# POWER.net
KiCad netlist of a schematic drawn in Altium Designer
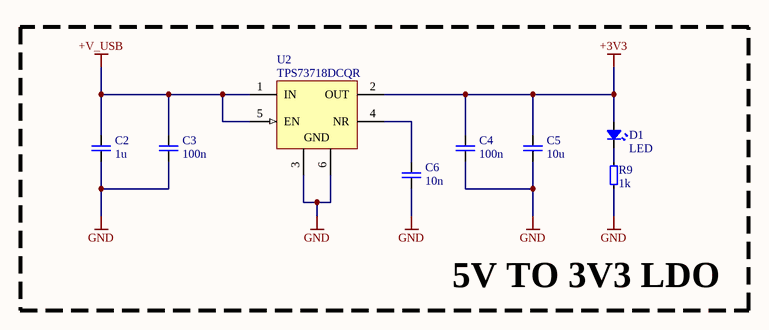
[diagram p0: POWER.SchDoc]

(export (version "E")
  (design (tool "Eeschema 10.0.6"))
  (components
    (comp (ref "C2")
      (value "1u")
      (footprint "C0603")
      (description "Generic 0603 SMD Ceramic Capacitor")
      (libsource (lib "PolSl Racing - Electrical") (part "Capacitor"))
    )
    (comp (ref "C3")
      (value "100n")
      (footprint "C0603")
      (description "Generic 0603 SMD Ceramic Capacitor")
      (libsource (lib "PolSl Racing - Electrical") (part "Capacitor"))
    )
    (comp (ref "C4")
      (value "100n")
      (footprint "C0603")
      (description "Generic 0603 SMD Ceramic Capacitor")
      (libsource (lib "PolSl Racing - Electrical") (part "Capacitor"))
    )
    (comp (ref "C5")
      (value "10u")
      (footprint "C0805")
      (description "Generic 0805 SMD Ceramic Capacitor")
      (libsource (lib "PolSl Racing - Electrical") (part "Capacitor"))
    )
    (comp (ref "C6")
      (value "10n")
      (footprint "C0603")
      (description "Generic 0603 SMD Ceramic Capacitor")
      (libsource (lib "PolSl Racing - Electrical") (part "Capacitor"))
    )
    (comp (ref "D1")
      (value "LED")
      (footprint "LED0603")
      (description "0603 LED")
      (libsource (lib "PolSl Racing - Electrical") (part "LED"))
    )
    (comp (ref "R9")
      (value "1k")
      (footprint "R0603")
      (description "Generic 0603 SMD Resistor")
      (libsource (lib "PolSl Racing - Electrical") (part "Resistor"))
    )
    (comp (ref "U2")
      (value "TPS73718DCQR")
      (footprint "DCQ0006A_L")
      (fields (field (name "MANUFACTURER") "Texas Instruments"))
      (libsource (lib "Altium Content Vault") (part "TI-TPS73XXXDCQ6"))
    )
  )
  (nets
    (net (code "1") (name "+3V3") (class "Default")
      (node (ref "C4") (pin "2") (pinfunction "2_2") (pintype "passive"))
      (node (ref "C5") (pin "2") (pinfunction "2_2") (pintype "passive"))
      (node (ref "D1") (pin "A") (pinfunction "A_A") (pintype "passive"))
      (node (ref "U2") (pin "2") (pinfunction "OUT_2") (pintype "power_in"))
    )
    (net (code "2") (name "+V_USB") (class "Default")
      (node (ref "C2") (pin "2") (pinfunction "2_2") (pintype "passive"))
      (node (ref "C3") (pin "2") (pinfunction "2_2") (pintype "passive"))
      (node (ref "U2") (pin "1") (pinfunction "IN_1") (pintype "power_in"))
      (node (ref "U2") (pin "5") (pinfunction "EN_5") (pintype "input"))
    )
    (net (code "3") (name "GND") (class "Default")
      (node (ref "C2") (pin "1") (pinfunction "1_1") (pintype "passive"))
      (node (ref "C3") (pin "1") (pinfunction "1_1") (pintype "passive"))
      (node (ref "C4") (pin "1") (pinfunction "1_1") (pintype "passive"))
      (node (ref "C5") (pin "1") (pinfunction "1_1") (pintype "passive"))
      (node (ref "C6") (pin "1") (pinfunction "1_1") (pintype "passive"))
      (node (ref "R9") (pin "1") (pinfunction "1_1") (pintype "passive"))
      (node (ref "U2") (pin "3") (pinfunction "GND_3") (pintype "power_in"))
      (node (ref "U2") (pin "6") (pinfunction "GND_6") (pintype "power_in"))
    )
    (net (code "4") (name "Net-(D1-PadK)") (class "Default")
      (node (ref "D1") (pin "K") (pinfunction "K_K") (pintype "passive"))
      (node (ref "R9") (pin "2") (pinfunction "2_2") (pintype "passive"))
    )
    (net (code "5") (name "Net-(U2-NR)") (class "Default")
      (node (ref "C6") (pin "2") (pinfunction "2_2") (pintype "passive"))
      (node (ref "U2") (pin "4") (pinfunction "NR_4") (pintype "passive"))
    )
  )
)
